# Schematic.net
KiCad netlist of a schematic drawn in EasyEDA
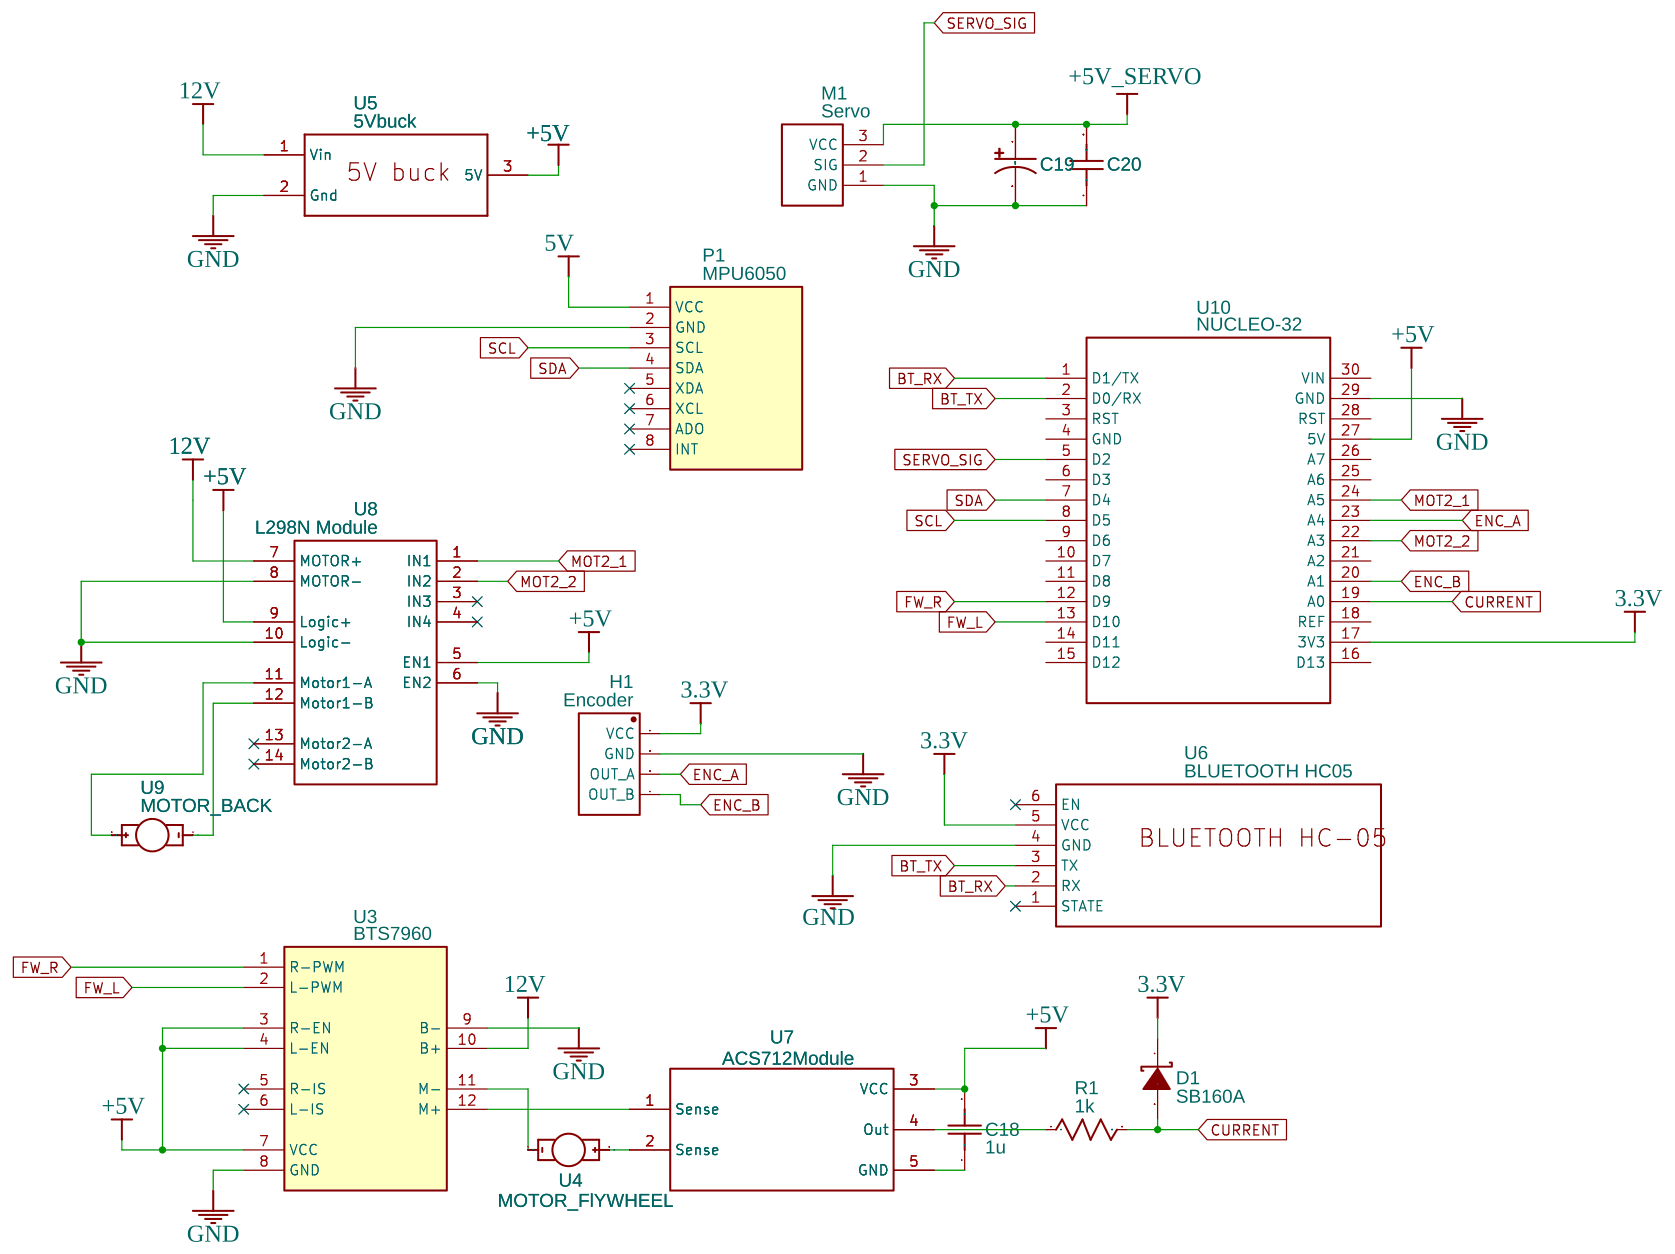
[diagram p0: schematic sheet]

(export (version "E")
  (design (tool "Eeschema 10.0.6"))
  (components
    (comp (ref "C18") (value "1u") (libsource (lib "") (part "Cap_RAD-0.1_US")))
    (comp (ref "C19") (value "1u") (libsource (lib "") (part "Cap_Electrolytic(TH)_D3.0XF1.5_US")))
    (comp (ref "C20") (value "1u") (libsource (lib "") (part "Cap_RAD-0.1_US")))
    (comp (ref "D1")
      (value "SB160A")
      (fields (field (name "BOM_Supplier Part") "C15614"))
      (libsource (lib "") (part "SB160A"))
    )
    (comp (ref "H1")
      (value "Encoder")
      (fields
        (field (name "BOM_Manufacturer Part") "210S-1*4P L=11.6MMGold-plated black")
        (field (name "BOM_Supplier Part") "C124378")
      )
      (libsource (lib "") (part "Header-Male-2.54_1x4"))
    )
    (comp (ref "M1")
      (value "Servo")
      (fields (field (name "BOM_Manufacturer Part") "New SchematicLib"))
      (libsource (lib "") (part "Unknown_685_155"))
    )
    (comp (ref "P1") (value "MPU6050") (libsource (lib "") (part "Unknown_610_250")))
    (comp (ref "R1") (value "1k") (libsource (lib "") (part "Res_AXIAL-0.3(1/8W)_US")))
    (comp (ref "U3") (value "BTS7960") (libsource (lib "") (part "Unknown_370_540")))
    (comp (ref "U4") (value "MOTOR_FlYWHEEL") (libsource (lib "") (part "Unknown_530_630")))
    (comp (ref "U5") (value "5Vbuck") (libsource (lib "") (part "Unknown_400_130")))
    (comp (ref "U6") (value "BLUETOOTH HC05") (libsource (lib "") (part "Unknown_820_475")))
    (comp (ref "U7")
      (value "ACS712Module")
      (fields (field (name "BOM_Manufacturer Part") "AC712Module"))
      (libsource (lib "") (part "Unknown_640_610"))
    )
    (comp (ref "U8") (value "L298N Module") (libsource (lib "") (part "Unknown_465_330")))
    (comp (ref "U9") (value "MOTOR_BACK") (libsource (lib "") (part "Unknown_325_475")))
    (comp (ref "U10") (value "NUCLEO-32") (libsource (lib "") (part "NUCLEO STM32F303K8 MINUCY")))
  )
  (nets
    (net (code "1") (name "+5V") (class "Default")
      (node (ref "C18") (pin "2") (pinfunction "2_2") (pintype "unspecified"))
      (node (ref "U10") (pin "27") (pinfunction "5V_27") (pintype "unspecified"))
      (node (ref "U3") (pin "3") (pinfunction "R-EN_3") (pintype "unspecified"))
      (node (ref "U3") (pin "4") (pinfunction "L-EN_4") (pintype "unspecified"))
      (node (ref "U3") (pin "7") (pinfunction "VCC_7") (pintype "unspecified"))
      (node (ref "U5") (pin "3") (pinfunction "5V_3") (pintype "unspecified"))
      (node (ref "U7") (pin "3") (pinfunction "VCC_3") (pintype "unspecified"))
      (node (ref "U8") (pin "5") (pinfunction "EN1_5") (pintype "unspecified"))
      (node (ref "U8") (pin "9") (pinfunction "Logic+_9") (pintype "unspecified"))
    )
    (net (code "2") (name "+5V_SERVO") (class "Default")
      (node (ref "C19") (pin "1") (pinfunction "1_1") (pintype "unspecified"))
      (node (ref "C20") (pin "2") (pinfunction "2_2") (pintype "unspecified"))
      (node (ref "M1") (pin "3") (pinfunction "VCC_3") (pintype "unspecified"))
    )
    (net (code "3") (name "3.3V") (class "Default")
      (node (ref "D1") (pin "1") (pinfunction "K_1") (pintype "unspecified"))
      (node (ref "H1") (pin "1") (pinfunction "VCC_1") (pintype "unspecified"))
      (node (ref "U10") (pin "17") (pinfunction "3V3_17") (pintype "unspecified"))
      (node (ref "U6") (pin "5") (pinfunction "VCC_5") (pintype "unspecified"))
    )
    (net (code "4") (name "5V") (class "Default")
      (node (ref "P1") (pin "1") (pinfunction "VCC_1") (pintype "unspecified"))
    )
    (net (code "5") (name "12V") (class "Default")
      (node (ref "U3") (pin "10") (pinfunction "B+_10") (pintype "unspecified"))
      (node (ref "U5") (pin "1") (pinfunction "Vin_1") (pintype "unspecified"))
      (node (ref "U8") (pin "7") (pinfunction "MOTOR+_7") (pintype "unspecified"))
    )
    (net (code "6") (name "BT_RX") (class "Default")
      (node (ref "U10") (pin "1") (pinfunction "D1/TX_1") (pintype "unspecified"))
      (node (ref "U6") (pin "2") (pinfunction "RX_2") (pintype "unspecified"))
    )
    (net (code "7") (name "BT_TX") (class "Default")
      (node (ref "U10") (pin "2") (pinfunction "D0/RX_2") (pintype "unspecified"))
      (node (ref "U6") (pin "3") (pinfunction "TX_3") (pintype "unspecified"))
    )
    (net (code "8") (name "CURRENT") (class "Default")
      (node (ref "D1") (pin "2") (pinfunction "A_2") (pintype "unspecified"))
      (node (ref "R1") (pin "2") (pinfunction "2_2") (pintype "unspecified"))
      (node (ref "U10") (pin "19") (pinfunction "A0_19") (pintype "unspecified"))
    )
    (net (code "9") (name "ENC_A") (class "Default")
      (node (ref "H1") (pin "3") (pinfunction "OUT_A_3") (pintype "unspecified"))
      (node (ref "U10") (pin "23") (pinfunction "A4_23") (pintype "unspecified"))
    )
    (net (code "10") (name "ENC_B") (class "Default")
      (node (ref "H1") (pin "4") (pinfunction "OUT_B_4") (pintype "unspecified"))
      (node (ref "U10") (pin "20") (pinfunction "A1_20") (pintype "unspecified"))
    )
    (net (code "11") (name "FW_L") (class "Default")
      (node (ref "U10") (pin "13") (pinfunction "D10_13") (pintype "unspecified"))
      (node (ref "U3") (pin "2") (pinfunction "L-PWM_2") (pintype "unspecified"))
    )
    (net (code "12") (name "FW_R") (class "Default")
      (node (ref "U10") (pin "12") (pinfunction "D9_12") (pintype "unspecified"))
      (node (ref "U3") (pin "1") (pinfunction "R-PWM_1") (pintype "unspecified"))
    )
    (net (code "13") (name "GND") (class "Default")
      (node (ref "C19") (pin "2") (pinfunction "2_2") (pintype "unspecified"))
      (node (ref "C20") (pin "1") (pinfunction "1_1") (pintype "unspecified"))
      (node (ref "H1") (pin "2") (pinfunction "GND_2") (pintype "unspecified"))
      (node (ref "M1") (pin "1") (pinfunction "GND_1") (pintype "unspecified"))
      (node (ref "P1") (pin "2") (pinfunction "GND_2") (pintype "unspecified"))
      (node (ref "U10") (pin "29") (pinfunction "GND_29") (pintype "unspecified"))
      (node (ref "U3") (pin "8") (pinfunction "GND_8") (pintype "unspecified"))
      (node (ref "U3") (pin "9") (pinfunction "B-_9") (pintype "unspecified"))
      (node (ref "U5") (pin "2") (pinfunction "Gnd_2") (pintype "unspecified"))
      (node (ref "U6") (pin "4") (pinfunction "GND_4") (pintype "unspecified"))
      (node (ref "U8") (pin "10") (pinfunction "Logic-_10") (pintype "unspecified"))
      (node (ref "U8") (pin "6") (pinfunction "EN2_6") (pintype "unspecified"))
      (node (ref "U8") (pin "8") (pinfunction "MOTOR-_8") (pintype "unspecified"))
    )
    (net (code "14") (name "MOT2_1") (class "Default")
      (node (ref "U10") (pin "24") (pinfunction "A5_24") (pintype "unspecified"))
      (node (ref "U8") (pin "1") (pinfunction "IN1_1") (pintype "unspecified"))
    )
    (net (code "15") (name "MOT2_2") (class "Default")
      (node (ref "U10") (pin "22") (pinfunction "A3_22") (pintype "unspecified"))
      (node (ref "U8") (pin "2") (pinfunction "IN2_2") (pintype "unspecified"))
    )
    (net (code "16") (name "Net-(U3-M+)") (class "Default")
      (node (ref "U3") (pin "12") (pinfunction "M+_12") (pintype "unspecified"))
      (node (ref "U7") (pin "1") (pinfunction "Sense_1") (pintype "unspecified"))
    )
    (net (code "17") (name "Net-(U3-M-)") (class "Default")
      (node (ref "U3") (pin "11") (pinfunction "M-_11") (pintype "unspecified"))
      (node (ref "U4") (pin "-") (pinfunction "-_-") (pintype "unspecified"))
    )
    (net (code "18") (name "Net-(U4-Pad+)") (class "Default")
      (node (ref "U4") (pin "+") (pinfunction "+_+") (pintype "unspecified"))
      (node (ref "U7") (pin "2") (pinfunction "Sense_2") (pintype "unspecified"))
    )
    (net (code "19") (name "Net-(U7-GND)") (class "Default")
      (node (ref "C18") (pin "1") (pinfunction "1_1") (pintype "unspecified"))
      (node (ref "U7") (pin "5") (pinfunction "GND_5") (pintype "unspecified"))
    )
    (net (code "20") (name "Net-(U7-Out)") (class "Default")
      (node (ref "R1") (pin "1") (pinfunction "1_1") (pintype "unspecified"))
      (node (ref "U7") (pin "4") (pinfunction "Out_4") (pintype "unspecified"))
    )
    (net (code "21") (name "Net-(U8-Motor1-A)") (class "Default")
      (node (ref "U8") (pin "11") (pinfunction "Motor1-A_11") (pintype "unspecified"))
      (node (ref "U9") (pin "+") (pinfunction "+_+") (pintype "unspecified"))
    )
    (net (code "22") (name "Net-(U8-Motor1-B)") (class "Default")
      (node (ref "U8") (pin "12") (pinfunction "Motor1-B_12") (pintype "unspecified"))
      (node (ref "U9") (pin "-") (pinfunction "-_-") (pintype "unspecified"))
    )
    (net (code "23") (name "SCL") (class "Default")
      (node (ref "P1") (pin "3") (pinfunction "SCL_3") (pintype "unspecified"))
      (node (ref "U10") (pin "8") (pinfunction "D5_8") (pintype "unspecified"))
    )
    (net (code "24") (name "SDA") (class "Default")
      (node (ref "P1") (pin "4") (pinfunction "SDA_4") (pintype "unspecified"))
      (node (ref "U10") (pin "7") (pinfunction "D4_7") (pintype "unspecified"))
    )
    (net (code "25") (name "SERVO_SIG") (class "Default")
      (node (ref "M1") (pin "2") (pinfunction "SIG_2") (pintype "unspecified"))
      (node (ref "U10") (pin "5") (pinfunction "D2_5") (pintype "unspecified"))
    )
    (net (code "26") (name "unconnected-(P1-ADO-Pad7)") (class "Default")
      (node (ref "P1") (pin "7") (pinfunction "ADO_7") (pintype "unspecified+no_connect"))
    )
    (net (code "27") (name "unconnected-(P1-INT-Pad8)") (class "Default")
      (node (ref "P1") (pin "8") (pinfunction "INT_8") (pintype "unspecified+no_connect"))
    )
    (net (code "28") (name "unconnected-(P1-XCL-Pad6)") (class "Default")
      (node (ref "P1") (pin "6") (pinfunction "XCL_6") (pintype "unspecified+no_connect"))
    )
    (net (code "29") (name "unconnected-(P1-XDA-Pad5)") (class "Default")
      (node (ref "P1") (pin "5") (pinfunction "XDA_5") (pintype "unspecified+no_connect"))
    )
    (net (code "30") (name "unconnected-(U3-L-IS-Pad6)") (class "Default")
      (node (ref "U3") (pin "6") (pinfunction "L-IS_6") (pintype "unspecified+no_connect"))
    )
    (net (code "31") (name "unconnected-(U3-R-IS-Pad5)") (class "Default")
      (node (ref "U3") (pin "5") (pinfunction "R-IS_5") (pintype "unspecified+no_connect"))
    )
    (net (code "32") (name "unconnected-(U6-EN-Pad6)") (class "Default")
      (node (ref "U6") (pin "6") (pinfunction "EN_6") (pintype "unspecified+no_connect"))
    )
    (net (code "33") (name "unconnected-(U6-STATE-Pad1)") (class "Default")
      (node (ref "U6") (pin "1") (pinfunction "STATE_1") (pintype "unspecified+no_connect"))
    )
    (net (code "34") (name "unconnected-(U8-IN3-Pad3)") (class "Default")
      (node (ref "U8") (pin "3") (pinfunction "IN3_3") (pintype "unspecified+no_connect"))
    )
    (net (code "35") (name "unconnected-(U8-IN4-Pad4)") (class "Default")
      (node (ref "U8") (pin "4") (pinfunction "IN4_4") (pintype "unspecified+no_connect"))
    )
    (net (code "36") (name "unconnected-(U8-Motor2-A-Pad13)") (class "Default")
      (node (ref "U8") (pin "13") (pinfunction "Motor2-A_13") (pintype "unspecified+no_connect"))
    )
    (net (code "37") (name "unconnected-(U8-Motor2-B-Pad14)") (class "Default")
      (node (ref "U8") (pin "14") (pinfunction "Motor2-B_14") (pintype "unspecified+no_connect"))
    )
    (net (code "38") (name "unconnected-(U10-A2-Pad21)") (class "Default")
      (node (ref "U10") (pin "21") (pinfunction "A2_21") (pintype "unspecified"))
    )
    (net (code "39") (name "unconnected-(U10-A6-Pad25)") (class "Default")
      (node (ref "U10") (pin "25") (pinfunction "A6_25") (pintype "unspecified"))
    )
    (net (code "40") (name "unconnected-(U10-A7-Pad26)") (class "Default")
      (node (ref "U10") (pin "26") (pinfunction "A7_26") (pintype "unspecified"))
    )
    (net (code "41") (name "unconnected-(U10-D3-Pad6)") (class "Default")
      (node (ref "U10") (pin "6") (pinfunction "D3_6") (pintype "unspecified"))
    )
    (net (code "42") (name "unconnected-(U10-D6-Pad9)") (class "Default")
      (node (ref "U10") (pin "9") (pinfunction "D6_9") (pintype "unspecified"))
    )
    (net (code "43") (name "unconnected-(U10-D7-Pad10)") (class "Default")
      (node (ref "U10") (pin "10") (pinfunction "D7_10") (pintype "unspecified"))
    )
    (net (code "44") (name "unconnected-(U10-D8-Pad11)") (class "Default")
      (node (ref "U10") (pin "11") (pinfunction "D8_11") (pintype "unspecified"))
    )
    (net (code "45") (name "unconnected-(U10-D11-Pad14)") (class "Default")
      (node (ref "U10") (pin "14") (pinfunction "D11_14") (pintype "unspecified"))
    )
    (net (code "46") (name "unconnected-(U10-D12-Pad15)") (class "Default")
      (node (ref "U10") (pin "15") (pinfunction "D12_15") (pintype "unspecified"))
    )
    (net (code "47") (name "unconnected-(U10-D13-Pad16)") (class "Default")
      (node (ref "U10") (pin "16") (pinfunction "D13_16") (pintype "unspecified"))
    )
    (net (code "48") (name "unconnected-(U10-GND-Pad4)") (class "Default")
      (node (ref "U10") (pin "4") (pinfunction "GND_4") (pintype "unspecified"))
    )
    (net (code "49") (name "unconnected-(U10-REF-Pad18)") (class "Default")
      (node (ref "U10") (pin "18") (pinfunction "REF_18") (pintype "unspecified"))
    )
    (net (code "50") (name "unconnected-(U10-RST-Pad3)") (class "Default")
      (node (ref "U10") (pin "3") (pinfunction "RST_3") (pintype "unspecified"))
    )
    (net (code "51") (name "unconnected-(U10-RST-Pad28)") (class "Default")
      (node (ref "U10") (pin "28") (pinfunction "RST_28") (pintype "unspecified"))
    )
    (net (code "52") (name "unconnected-(U10-VIN-Pad30)") (class "Default")
      (node (ref "U10") (pin "30") (pinfunction "VIN_30") (pintype "unspecified"))
    )
  )
)
